# iA-Pmod-AES3-4x4.net
KiCad netlist of a schematic drawn in Altium Designer
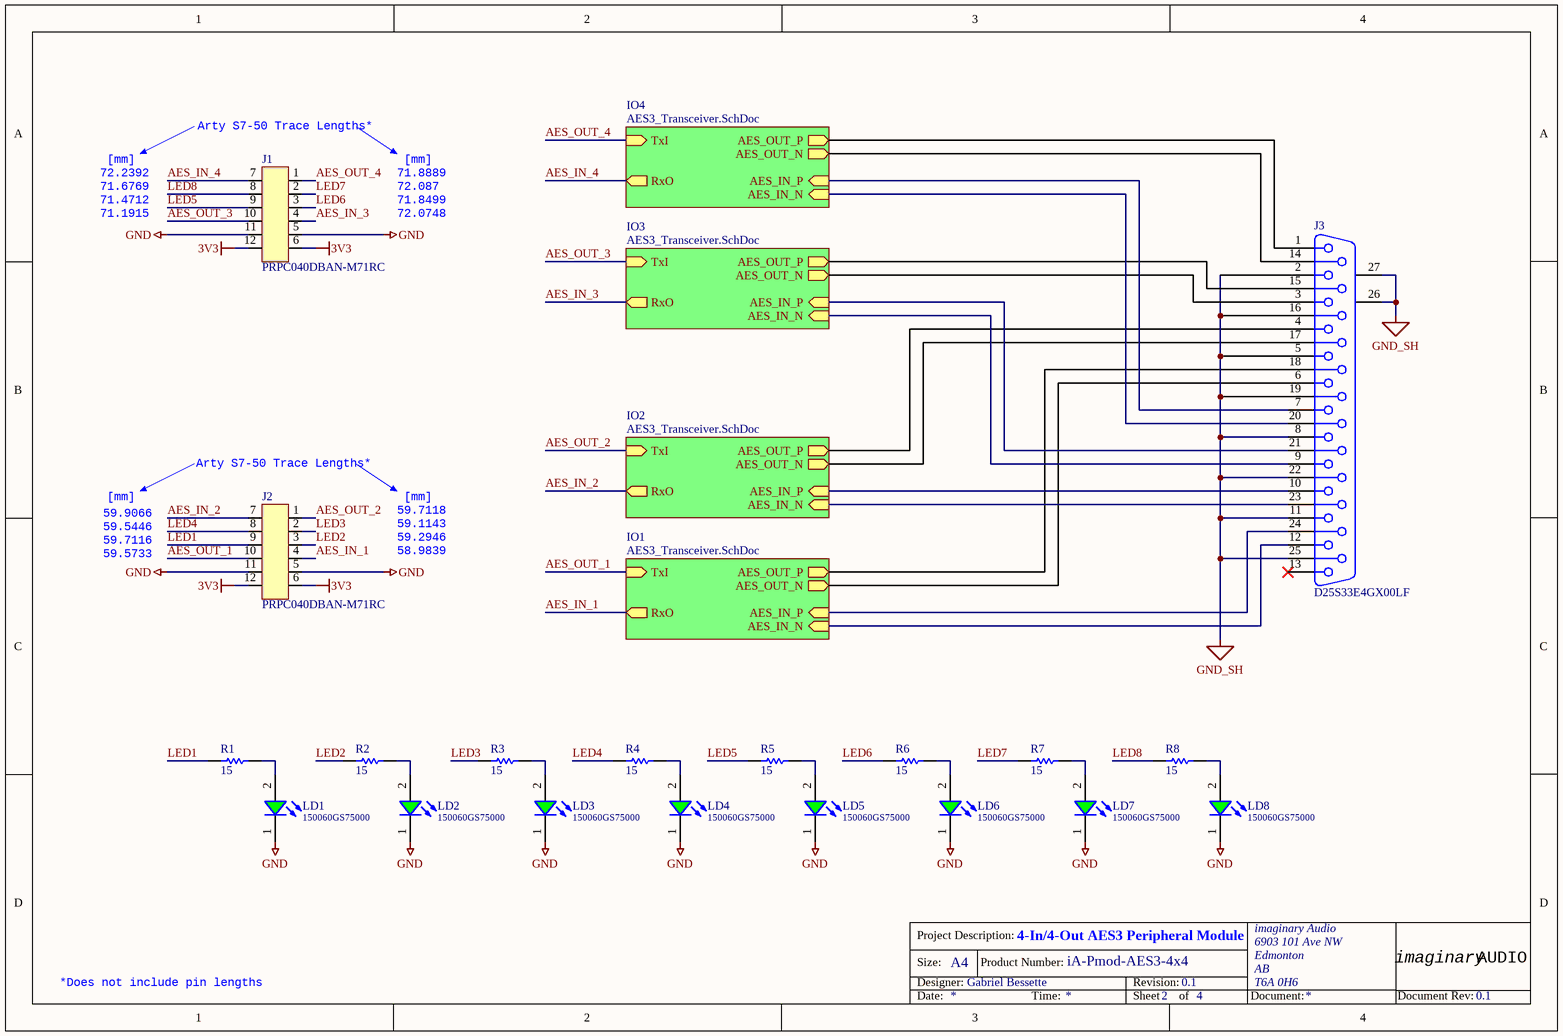
[diagram p0: iA-Pmod-AES3-4x4.SchDoc]

(export (version "E")
  (design (tool "Eeschema 10.0.6"))
  (components
    (comp (ref "J1")
      (value "PRPC040DBAN-M71RC")
      (footprint "HDRMTH100RA_6x2")
      (description "CONN HEADER .100 DUAL R/A 80POS")
      (fields (field (name "MANUFACTURER") "Sullins"))
      (libsource (lib "iA-IntLib") (part "HDRMTH100RA_6X2"))
    )
    (comp (ref "J2")
      (value "PRPC040DBAN-M71RC")
      (footprint "HDRMTH100RA_6x2")
      (description "CONN HEADER .100 DUAL R/A 80POS")
      (fields (field (name "MANUFACTURER") "Sullins"))
      (libsource (lib "iA-IntLib") (part "HDRMTH100RA_6X2"))
    )
    (comp (ref "J3")
      (value "D25S33E4GX00LF")
      (footprint "D25S33E4GX00LF")
      (description "CONN, D-SUB RCPT 25POS R/A SOLDER")
      (fields (field (name "MANUFACTURER") "Amphenol FCI") (field (name "PUBLISHER") "Altium Limited"))
      (libsource (lib "iA-IntLib") (part "D25S33E4GX00LF"))
    )
    (comp (ref "LD1")
      (value "150060GS75000")
      (footprint "WL-SMCW_0603_H=0.7mm")
      (description "WURTH ELEKTRONIK - 150060GS75000 - LED, Green, 520 nm, 3.2 V, 30 mA, 430 mcd RoHS Compliant: Yes")
      (fields (field (name "MANUFACTURER") "Wurth Electronics") (field (name "PUBLISHER") "Wurth Elektronik"))
      (libsource (lib "iA-IntLib") (part "150060GS75000"))
    )
    (comp (ref "LD2")
      (value "150060GS75000")
      (footprint "WL-SMCW_0603_H=0.7mm")
      (description "WURTH ELEKTRONIK - 150060GS75000 - LED, Green, 520 nm, 3.2 V, 30 mA, 430 mcd RoHS Compliant: Yes")
      (fields (field (name "MANUFACTURER") "Wurth Electronics") (field (name "PUBLISHER") "Wurth Elektronik"))
      (libsource (lib "iA-IntLib") (part "150060GS75000"))
    )
    (comp (ref "LD3")
      (value "150060GS75000")
      (footprint "WL-SMCW_0603_H=0.7mm")
      (description "WURTH ELEKTRONIK - 150060GS75000 - LED, Green, 520 nm, 3.2 V, 30 mA, 430 mcd RoHS Compliant: Yes")
      (fields (field (name "MANUFACTURER") "Wurth Electronics") (field (name "PUBLISHER") "Wurth Elektronik"))
      (libsource (lib "iA-IntLib") (part "150060GS75000"))
    )
    (comp (ref "LD4")
      (value "150060GS75000")
      (footprint "WL-SMCW_0603_H=0.7mm")
      (description "WURTH ELEKTRONIK - 150060GS75000 - LED, Green, 520 nm, 3.2 V, 30 mA, 430 mcd RoHS Compliant: Yes")
      (fields (field (name "MANUFACTURER") "Wurth Electronics") (field (name "PUBLISHER") "Wurth Elektronik"))
      (libsource (lib "iA-IntLib") (part "150060GS75000"))
    )
    (comp (ref "LD5")
      (value "150060GS75000")
      (footprint "WL-SMCW_0603_H=0.7mm")
      (description "WURTH ELEKTRONIK - 150060GS75000 - LED, Green, 520 nm, 3.2 V, 30 mA, 430 mcd RoHS Compliant: Yes")
      (fields (field (name "MANUFACTURER") "Wurth Electronics") (field (name "PUBLISHER") "Wurth Elektronik"))
      (libsource (lib "iA-IntLib") (part "150060GS75000"))
    )
    (comp (ref "LD6")
      (value "150060GS75000")
      (footprint "WL-SMCW_0603_H=0.7mm")
      (description "WURTH ELEKTRONIK - 150060GS75000 - LED, Green, 520 nm, 3.2 V, 30 mA, 430 mcd RoHS Compliant: Yes")
      (fields (field (name "MANUFACTURER") "Wurth Electronics") (field (name "PUBLISHER") "Wurth Elektronik"))
      (libsource (lib "iA-IntLib") (part "150060GS75000"))
    )
    (comp (ref "LD7")
      (value "150060GS75000")
      (footprint "WL-SMCW_0603_H=0.7mm")
      (description "WURTH ELEKTRONIK - 150060GS75000 - LED, Green, 520 nm, 3.2 V, 30 mA, 430 mcd RoHS Compliant: Yes")
      (fields (field (name "MANUFACTURER") "Wurth Electronics") (field (name "PUBLISHER") "Wurth Elektronik"))
      (libsource (lib "iA-IntLib") (part "150060GS75000"))
    )
    (comp (ref "LD8")
      (value "150060GS75000")
      (footprint "WL-SMCW_0603_H=0.7mm")
      (description "WURTH ELEKTRONIK - 150060GS75000 - LED, Green, 520 nm, 3.2 V, 30 mA, 430 mcd RoHS Compliant: Yes")
      (fields (field (name "MANUFACTURER") "Wurth Electronics") (field (name "PUBLISHER") "Wurth Elektronik"))
      (libsource (lib "iA-IntLib") (part "150060GS75000"))
    )
    (comp (ref "R1")
      (value "15")
      (footprint "RESC1608X55X30NL15T15")
      (description "Res Thick Film 0603 15 Ohm 1% 1/10W ±100ppm/°C Molded SMD Punched Carrier T/R")
      (fields (field (name "MANUFACTURER PART NUMBER") "ERJ-3EKF15R0V") (field (name "TOLERANCE") "1%"))
      (libsource (lib "iA-IntLib") (part "RES"))
    )
    (comp (ref "R2")
      (value "15")
      (footprint "RESC1608X55X30NL15T15")
      (description "Res Thick Film 0603 15 Ohm 1% 1/10W ±100ppm/°C Molded SMD Punched Carrier T/R")
      (fields (field (name "MANUFACTURER PART NUMBER") "ERJ-3EKF15R0V") (field (name "TOLERANCE") "1%"))
      (libsource (lib "iA-IntLib") (part "RES"))
    )
    (comp (ref "R3")
      (value "15")
      (footprint "RESC1608X55X30NL15T15")
      (description "Res Thick Film 0603 15 Ohm 1% 1/10W ±100ppm/°C Molded SMD Punched Carrier T/R")
      (fields (field (name "MANUFACTURER PART NUMBER") "ERJ-3EKF15R0V") (field (name "TOLERANCE") "1%"))
      (libsource (lib "iA-IntLib") (part "RES"))
    )
    (comp (ref "R4")
      (value "15")
      (footprint "RESC1608X55X30NL15T15")
      (description "Res Thick Film 0603 15 Ohm 1% 1/10W ±100ppm/°C Molded SMD Punched Carrier T/R")
      (fields (field (name "MANUFACTURER PART NUMBER") "ERJ-3EKF15R0V") (field (name "TOLERANCE") "1%"))
      (libsource (lib "iA-IntLib") (part "RES"))
    )
    (comp (ref "R5")
      (value "15")
      (footprint "RESC1608X55X30NL15T15")
      (description "Res Thick Film 0603 15 Ohm 1% 1/10W ±100ppm/°C Molded SMD Punched Carrier T/R")
      (fields (field (name "MANUFACTURER PART NUMBER") "ERJ-3EKF15R0V") (field (name "TOLERANCE") "1%"))
      (libsource (lib "iA-IntLib") (part "RES"))
    )
    (comp (ref "R6")
      (value "15")
      (footprint "RESC1608X55X30NL15T15")
      (description "Res Thick Film 0603 15 Ohm 1% 1/10W ±100ppm/°C Molded SMD Punched Carrier T/R")
      (fields (field (name "MANUFACTURER PART NUMBER") "ERJ-3EKF15R0V") (field (name "TOLERANCE") "1%"))
      (libsource (lib "iA-IntLib") (part "RES"))
    )
    (comp (ref "R7")
      (value "15")
      (footprint "RESC1608X55X30NL15T15")
      (description "Res Thick Film 0603 15 Ohm 1% 1/10W ±100ppm/°C Molded SMD Punched Carrier T/R")
      (fields (field (name "MANUFACTURER PART NUMBER") "ERJ-3EKF15R0V") (field (name "TOLERANCE") "1%"))
      (libsource (lib "iA-IntLib") (part "RES"))
    )
    (comp (ref "R8")
      (value "15")
      (footprint "RESC1608X55X30NL15T15")
      (description "Res Thick Film 0603 15 Ohm 1% 1/10W ±100ppm/°C Molded SMD Punched Carrier T/R")
      (fields (field (name "MANUFACTURER PART NUMBER") "ERJ-3EKF15R0V") (field (name "TOLERANCE") "1%"))
      (libsource (lib "iA-IntLib") (part "RES"))
    )
  )
  (nets
    (net (code "1") (name "/AES_IN_1") (class "Default") (node (ref "J2") (pin "4") (pintype "passive")))
    (net (code "2") (name "/AES_IN_2") (class "Default") (node (ref "J2") (pin "7") (pintype "passive")))
    (net (code "3") (name "/AES_IN_3") (class "Default") (node (ref "J1") (pin "4") (pintype "passive")))
    (net (code "4") (name "/AES_IN_4") (class "Default") (node (ref "J1") (pin "7") (pintype "passive")))
    (net (code "5") (name "/AES_IN_N") (class "Default")
      (node (ref "J3") (pin "23") (pinfunction "23_23") (pintype "passive"))
    )
    (net (code "6") (name "/AES_IN_N_1") (class "Default")
      (node (ref "J3") (pin "12") (pinfunction "12_12") (pintype "passive"))
    )
    (net (code "7") (name "/AES_IN_N_2") (class "Default")
      (node (ref "J3") (pin "9") (pinfunction "9_9") (pintype "passive"))
    )
    (net (code "8") (name "/AES_IN_N_3") (class "Default")
      (node (ref "J3") (pin "20") (pinfunction "20_20") (pintype "passive"))
    )
    (net (code "9") (name "/AES_IN_P") (class "Default")
      (node (ref "J3") (pin "21") (pinfunction "21_21") (pintype "passive"))
    )
    (net (code "10") (name "/AES_IN_P_1") (class "Default")
      (node (ref "J3") (pin "24") (pinfunction "24_24") (pintype "passive"))
    )
    (net (code "11") (name "/AES_IN_P_2") (class "Default")
      (node (ref "J3") (pin "7") (pinfunction "7_7") (pintype "passive"))
    )
    (net (code "12") (name "/AES_IN_P_3") (class "Default")
      (node (ref "J3") (pin "10") (pinfunction "10_10") (pintype "passive"))
    )
    (net (code "13") (name "/AES_OUT_1") (class "Default") (node (ref "J2") (pin "10") (pintype "passive")))
    (net (code "14") (name "/AES_OUT_2") (class "Default") (node (ref "J2") (pin "1") (pintype "passive")))
    (net (code "15") (name "/AES_OUT_3") (class "Default") (node (ref "J1") (pin "10") (pintype "passive")))
    (net (code "16") (name "/AES_OUT_4") (class "Default") (node (ref "J1") (pin "1") (pintype "passive")))
    (net (code "17") (name "/AES_OUT_N") (class "Default")
      (node (ref "J3") (pin "17") (pinfunction "17_17") (pintype "passive"))
    )
    (net (code "18") (name "/AES_OUT_N_1") (class "Default")
      (node (ref "J3") (pin "3") (pinfunction "3_3") (pintype "passive"))
    )
    (net (code "19") (name "/AES_OUT_N_2") (class "Default")
      (node (ref "J3") (pin "14") (pinfunction "14_14") (pintype "passive"))
    )
    (net (code "20") (name "/AES_OUT_N_3") (class "Default")
      (node (ref "J3") (pin "6") (pinfunction "6_6") (pintype "passive"))
    )
    (net (code "21") (name "/AES_OUT_P") (class "Default")
      (node (ref "J3") (pin "18") (pinfunction "18_18") (pintype "passive"))
    )
    (net (code "22") (name "/AES_OUT_P_1") (class "Default")
      (node (ref "J3") (pin "15") (pinfunction "15_15") (pintype "passive"))
    )
    (net (code "23") (name "/AES_OUT_P_2") (class "Default")
      (node (ref "J3") (pin "1") (pinfunction "1_1") (pintype "passive"))
    )
    (net (code "24") (name "/AES_OUT_P_3") (class "Default")
      (node (ref "J3") (pin "4") (pinfunction "4_4") (pintype "passive"))
    )
    (net (code "25") (name "/LED1") (class "Default")
      (node (ref "J2") (pin "9") (pintype "passive"))
      (node (ref "R1") (pin "1") (pinfunction "1_1") (pintype "passive"))
    )
    (net (code "26") (name "/LED2") (class "Default")
      (node (ref "J2") (pin "3") (pintype "passive"))
      (node (ref "R2") (pin "1") (pinfunction "1_1") (pintype "passive"))
    )
    (net (code "27") (name "/LED3") (class "Default")
      (node (ref "J2") (pin "2") (pintype "passive"))
      (node (ref "R3") (pin "1") (pinfunction "1_1") (pintype "passive"))
    )
    (net (code "28") (name "/LED4") (class "Default")
      (node (ref "J2") (pin "8") (pintype "passive"))
      (node (ref "R4") (pin "1") (pinfunction "1_1") (pintype "passive"))
    )
    (net (code "29") (name "/LED5") (class "Default")
      (node (ref "J1") (pin "9") (pintype "passive"))
      (node (ref "R5") (pin "1") (pinfunction "1_1") (pintype "passive"))
    )
    (net (code "30") (name "/LED6") (class "Default")
      (node (ref "J1") (pin "3") (pintype "passive"))
      (node (ref "R6") (pin "1") (pinfunction "1_1") (pintype "passive"))
    )
    (net (code "31") (name "/LED7") (class "Default")
      (node (ref "J1") (pin "2") (pintype "passive"))
      (node (ref "R7") (pin "1") (pinfunction "1_1") (pintype "passive"))
    )
    (net (code "32") (name "/LED8") (class "Default")
      (node (ref "J1") (pin "8") (pintype "passive"))
      (node (ref "R8") (pin "1") (pinfunction "1_1") (pintype "passive"))
    )
    (net (code "33") (name "3V3") (class "Default")
      (node (ref "J1") (pin "12") (pintype "power_in"))
      (node (ref "J1") (pin "6") (pintype "power_in"))
      (node (ref "J2") (pin "12") (pintype "power_in"))
      (node (ref "J2") (pin "6") (pintype "power_in"))
    )
    (net (code "34") (name "GND") (class "Default")
      (node (ref "J1") (pin "11") (pintype "power_in"))
      (node (ref "J1") (pin "5") (pintype "power_in"))
      (node (ref "J2") (pin "11") (pintype "power_in"))
      (node (ref "J2") (pin "5") (pintype "power_in"))
      (node (ref "LD1") (pin "1") (pinfunction "K_1") (pintype "passive"))
      (node (ref "LD2") (pin "1") (pinfunction "K_1") (pintype "passive"))
      (node (ref "LD3") (pin "1") (pinfunction "K_1") (pintype "passive"))
      (node (ref "LD4") (pin "1") (pinfunction "K_1") (pintype "passive"))
      (node (ref "LD5") (pin "1") (pinfunction "K_1") (pintype "passive"))
      (node (ref "LD6") (pin "1") (pinfunction "K_1") (pintype "passive"))
      (node (ref "LD7") (pin "1") (pinfunction "K_1") (pintype "passive"))
      (node (ref "LD8") (pin "1") (pinfunction "K_1") (pintype "passive"))
    )
    (net (code "35") (name "GND_SH") (class "Default")
      (node (ref "J3") (pin "11") (pinfunction "11_11") (pintype "passive"))
      (node (ref "J3") (pin "16") (pinfunction "16_16") (pintype "passive"))
      (node (ref "J3") (pin "19") (pinfunction "19_19") (pintype "passive"))
      (node (ref "J3") (pin "2") (pinfunction "2_2") (pintype "passive"))
      (node (ref "J3") (pin "22") (pinfunction "22_22") (pintype "passive"))
      (node (ref "J3") (pin "25") (pinfunction "25_25") (pintype "passive"))
      (node (ref "J3") (pin "26") (pinfunction "MH1_26") (pintype "passive"))
      (node (ref "J3") (pin "27") (pinfunction "MH2_27") (pintype "passive"))
      (node (ref "J3") (pin "5") (pinfunction "5_5") (pintype "passive"))
      (node (ref "J3") (pin "8") (pinfunction "8_8") (pintype "passive"))
    )
    (net (code "36") (name "Net-(LD1-A)") (class "Default")
      (node (ref "LD1") (pin "2") (pinfunction "A_2") (pintype "passive"))
      (node (ref "R1") (pin "2") (pinfunction "2_2") (pintype "passive"))
    )
    (net (code "37") (name "Net-(LD2-A)") (class "Default")
      (node (ref "LD2") (pin "2") (pinfunction "A_2") (pintype "passive"))
      (node (ref "R2") (pin "2") (pinfunction "2_2") (pintype "passive"))
    )
    (net (code "38") (name "Net-(LD3-A)") (class "Default")
      (node (ref "LD3") (pin "2") (pinfunction "A_2") (pintype "passive"))
      (node (ref "R3") (pin "2") (pinfunction "2_2") (pintype "passive"))
    )
    (net (code "39") (name "Net-(LD4-A)") (class "Default")
      (node (ref "LD4") (pin "2") (pinfunction "A_2") (pintype "passive"))
      (node (ref "R4") (pin "2") (pinfunction "2_2") (pintype "passive"))
    )
    (net (code "40") (name "Net-(LD5-A)") (class "Default")
      (node (ref "LD5") (pin "2") (pinfunction "A_2") (pintype "passive"))
      (node (ref "R5") (pin "2") (pinfunction "2_2") (pintype "passive"))
    )
    (net (code "41") (name "Net-(LD6-A)") (class "Default")
      (node (ref "LD6") (pin "2") (pinfunction "A_2") (pintype "passive"))
      (node (ref "R6") (pin "2") (pinfunction "2_2") (pintype "passive"))
    )
    (net (code "42") (name "Net-(LD7-A)") (class "Default")
      (node (ref "LD7") (pin "2") (pinfunction "A_2") (pintype "passive"))
      (node (ref "R7") (pin "2") (pinfunction "2_2") (pintype "passive"))
    )
    (net (code "43") (name "Net-(LD8-A)") (class "Default")
      (node (ref "LD8") (pin "2") (pinfunction "A_2") (pintype "passive"))
      (node (ref "R8") (pin "2") (pinfunction "2_2") (pintype "passive"))
    )
    (net (code "44") (name "unconnected-(J3-Pad13)") (class "Default")
      (node (ref "J3") (pin "13") (pinfunction "13_13") (pintype "passive+no_connect"))
    )
  )
)
